# Adafruit_SMT_Datalogger_Shield_rev_C.net
KiCad netlist of a schematic drawn in Altium Designer
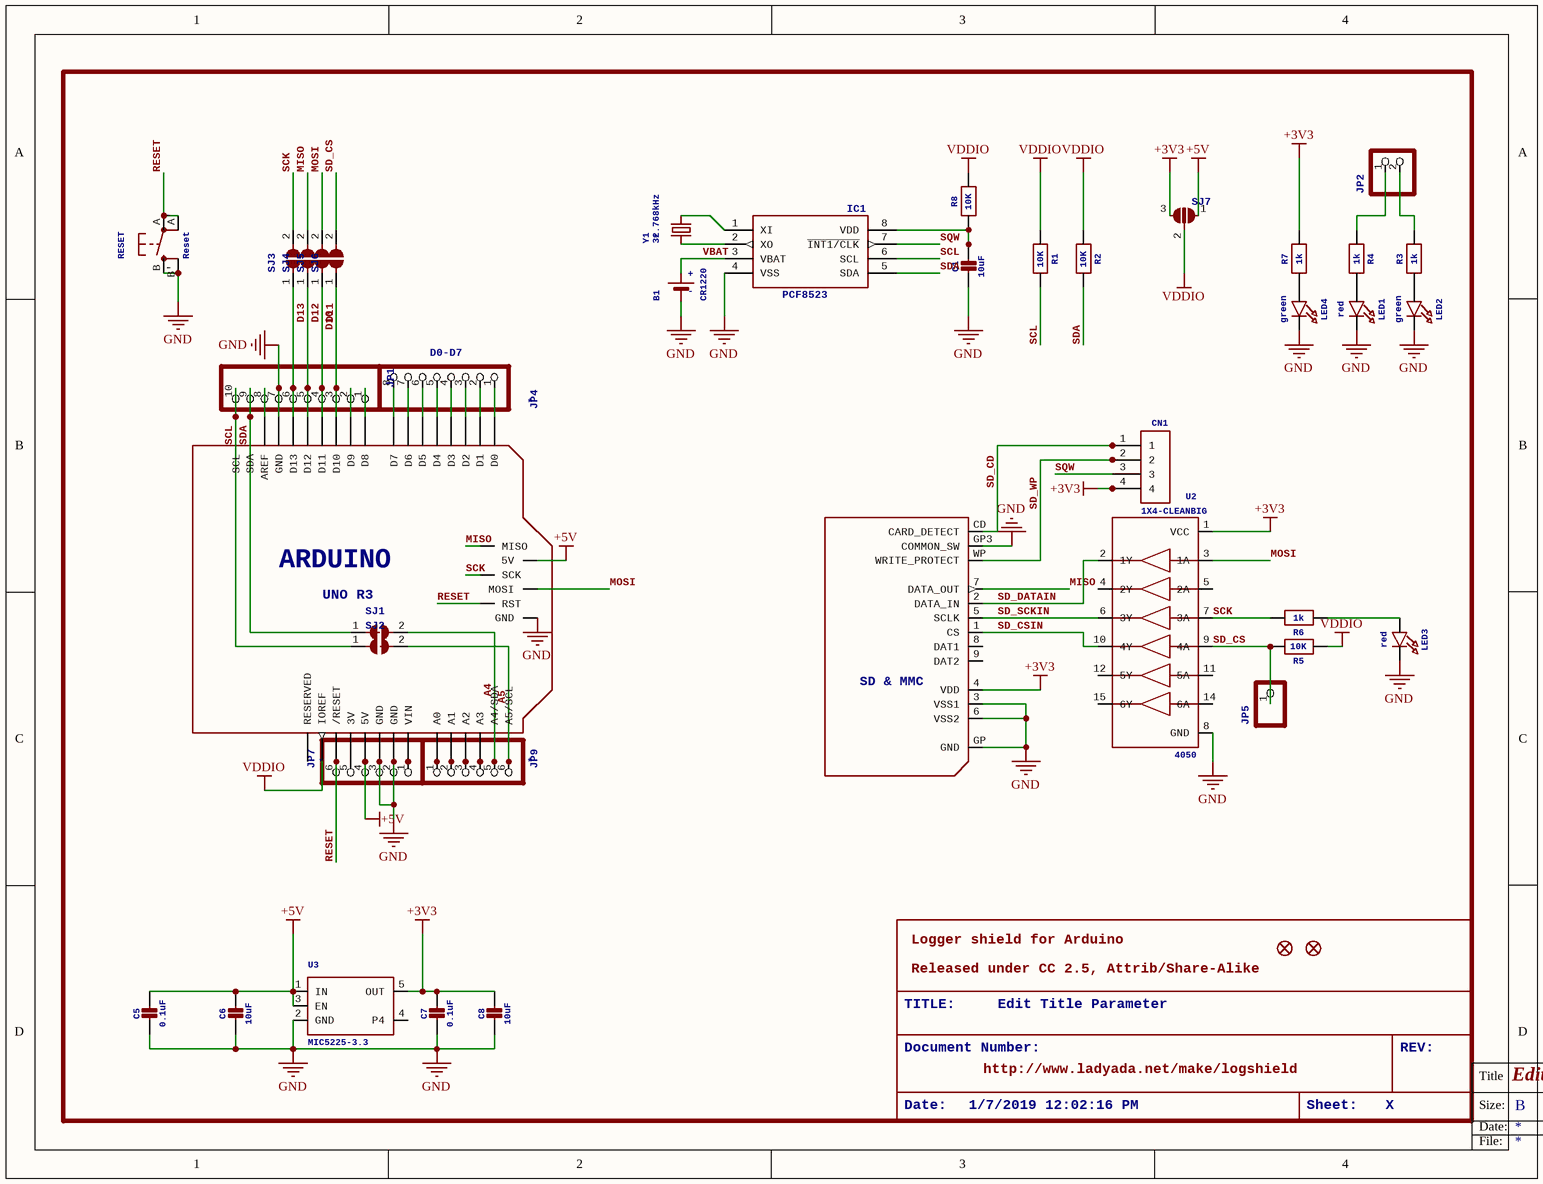
[diagram p0: Adafruit SMT Datalogger Shield rev C.SchDoc]

(export (version "E")
  (design (tool "Eeschema 10.0.6"))
  (components
    (comp (ref "B1")
      (value "CR1220")
      (footprint "CR1220")
      (fields (field (name "+") "+") (field (name "-") "-"))
      (libsource (lib "microbuilder") (part "BATTERYCR1220_SMT"))
    )
    (comp (ref "C1")
      (value "10uF")
      (footprint "0805-NO")
      (libsource (lib "microbuilder") (part "CAP_CERAMIC0805-NOOUTLINE"))
    )
    (comp (ref "C5")
      (value "0.1uF")
      (footprint "0805-NO")
      (libsource (lib "microbuilder") (part "CAP_CERAMIC0805-NOOUTLINE"))
    )
    (comp (ref "C6")
      (value "10uF")
      (footprint "0805-NO")
      (libsource (lib "microbuilder") (part "CAP_CERAMIC0805-NOOUTLINE"))
    )
    (comp (ref "C7")
      (value "0.1uF")
      (footprint "0805-NO")
      (libsource (lib "microbuilder") (part "CAP_CERAMIC0805-NOOUTLINE"))
    )
    (comp (ref "C8")
      (value "10uF")
      (footprint "0805-NO")
      (libsource (lib "microbuilder") (part "CAP_CERAMIC0805-NOOUTLINE"))
    )
    (comp (ref "CN1")
      (value "1X4-CLEANBIG")
      (footprint "1X04-CLEANBIG")
      (description "4-pin connector")
      (libsource (lib "adafruit") (part "1X4-CLEANBIG"))
    )
    (comp (ref "FID1")
      (value "FIDUCIAL_1MM")
      (footprint "FIDUCIAL_1MM")
      (description "Fiducial Alignment PointsVarious fiducial points for machine vision alignment.")
      (libsource (lib "microbuilder") (part "FIDUCIAL_1MM"))
    )
    (comp (ref "FID3")
      (value "FIDUCIAL_1MM")
      (footprint "FIDUCIAL_1MM")
      (description "Fiducial Alignment PointsVarious fiducial points for machine vision alignment.")
      (libsource (lib "microbuilder") (part "FIDUCIAL_1MM"))
    )
    (comp (ref "IC1")
      (value "PCF8523T")
      (footprint "SOIC8_150MIL")
      (fields (field (name "PCF8523") "PCF8523"))
      (libsource (lib "microbuilder") (part "RTC_PCF8523T"))
    )
    (comp (ref "JP1")
      (value "HEADER-1X1070MIL")
      (footprint "1X10_ROUND70")
      (description "PIN HEADER")
      (libsource (lib "microbuilder") (part "HEADER-1X1070MIL"))
    )
    (comp (ref "JP2")
      (value "HEADER-1X2ROUND")
      (footprint "1X02_ROUND")
      (description "PIN HEADER")
      (libsource (lib "microbuilder") (part "HEADER-1X2ROUND"))
    )
    (comp (ref "JP4")
      (value "D0-D7")
      (footprint "1X08-BIG")
      (description "PIN HEADER")
      (fields (field (name "NAME") "*"))
      (libsource (lib "adafruit") (part "PINHD-1X8BIG"))
    )
    (comp (ref "JP5")
      (value "HEADER-1X1ROUND")
      (footprint "1X01_ROUND")
      (description "PIN HEADER")
      (libsource (lib "microbuilder") (part "HEADER-1X1ROUND"))
    )
    (comp (ref "JP7")
      (value "PINHD-1X6B")
      (footprint "1X06-BIG")
      (description "PIN HEADER")
      (fields (field (name "NAME") "*"))
      (libsource (lib "adafruit") (part "PINHD-1X6B"))
    )
    (comp (ref "JP9")
      (value "PINHD-1X6B")
      (footprint "1X06-BIG")
      (description "PIN HEADER")
      (fields (field (name "NAME") "*"))
      (libsource (lib "adafruit") (part "PINHD-1X6B"))
    )
    (comp (ref "LED1")
      (value "red")
      (footprint "CHIPLED_0805_NOOUTLINE")
      (libsource (lib "microbuilder") (part "LED0805_NOOUTLINE"))
    )
    (comp (ref "LED2")
      (value "green")
      (footprint "CHIPLED_0805_NOOUTLINE")
      (libsource (lib "microbuilder") (part "LED0805_NOOUTLINE"))
    )
    (comp (ref "LED3")
      (value "red")
      (footprint "CHIPLED_0805_NOOUTLINE")
      (libsource (lib "microbuilder") (part "LED0805_NOOUTLINE"))
    )
    (comp (ref "LED4")
      (value "green")
      (footprint "CHIPLED_0805_NOOUTLINE")
      (libsource (lib "microbuilder") (part "LED0805_NOOUTLINE"))
    )
    (comp (ref "M1")
      (value "ARDUINO_R3_ICSP_NODIM")
      (footprint "ARDUINOR3_ICSP_NODIM")
      (fields (field (name "ARDUINO") "ARDUINO") (field (name "UNOR3") "UNO R3"))
      (libsource (lib "adafruit") (part "ARDUINO_R3_ICSP_NODIM"))
    )
    (comp (ref "R1")
      (value "10K")
      (footprint "0805-NO")
      (libsource (lib "microbuilder") (part "RESISTOR0805_NOOUTLINE"))
    )
    (comp (ref "R2")
      (value "10K")
      (footprint "0805-NO")
      (libsource (lib "microbuilder") (part "RESISTOR0805_NOOUTLINE"))
    )
    (comp (ref "R3")
      (value "1k")
      (footprint "0805-NO")
      (libsource (lib "microbuilder") (part "RESISTOR0805_NOOUTLINE"))
    )
    (comp (ref "R4")
      (value "1k")
      (footprint "0805-NO")
      (libsource (lib "microbuilder") (part "RESISTOR0805_NOOUTLINE"))
    )
    (comp (ref "R5")
      (value "10K")
      (footprint "0805-NO")
      (libsource (lib "microbuilder") (part "RESISTOR0805_NOOUTLINE"))
    )
    (comp (ref "R6")
      (value "1k")
      (footprint "0805-NO")
      (libsource (lib "microbuilder") (part "RESISTOR0805_NOOUTLINE"))
    )
    (comp (ref "R7")
      (value "1k")
      (footprint "0805-NO")
      (libsource (lib "microbuilder") (part "RESISTOR0805_NOOUTLINE"))
    )
    (comp (ref "R8")
      (value "10K")
      (footprint "0805-NO")
      (libsource (lib "microbuilder") (part "RESISTOR0805_NOOUTLINE"))
    )
    (comp (ref "RESET")
      (value "Reset")
      (footprint "EVQ-Q2_SMALLER")
      (description "SMT Tact Switches")
      (libsource (lib "microbuilder") (part "SWITCH_TACT_SMT_EVQQ2_SMALL"))
    )
    (comp (ref "SJ1")
      (value "SOLDERJUMPER")
      (footprint "SOLDERJUMPER_ARROW_NOPASTE")
      (libsource (lib "microbuilder") (part "SOLDERJUMPER"))
    )
    (comp (ref "SJ2")
      (value "SOLDERJUMPER")
      (footprint "SOLDERJUMPER_ARROW_NOPASTE")
      (libsource (lib "microbuilder") (part "SOLDERJUMPER"))
    )
    (comp (ref "SJ3")
      (value "SOLDERJUMPER")
      (footprint "SOLDERJUMPER_ARROW_NOPASTE")
      (libsource (lib "microbuilder") (part "SOLDERJUMPER"))
    )
    (comp (ref "SJ4")
      (value "SOLDERJUMPER")
      (footprint "SOLDERJUMPER_ARROW_NOPASTE")
      (libsource (lib "microbuilder") (part "SOLDERJUMPER"))
    )
    (comp (ref "SJ5")
      (value "SOLDERJUMPER")
      (footprint "SOLDERJUMPER_ARROW_NOPASTE")
      (libsource (lib "microbuilder") (part "SOLDERJUMPER"))
    )
    (comp (ref "SJ6")
      (value "SOLDERJUMPERCLOSED")
      (footprint "SOLDERJUMPER_CLOSEDWIRE")
      (libsource (lib "microbuilder") (part "SOLDERJUMPERCLOSED"))
    )
    (comp (ref "SJ7")
      (value "SOLDERJUMPER_2WAY")
      (footprint "SOLDERJUMPER_2WAY_OPEN_NOPASTE")
      (description "2-Way Solder Jumper")
      (libsource (lib "microbuilder") (part "SOLDERJUMPER_2WAY"))
    )
    (comp (ref "U$2")
      (value "SDMMC06132")
      (footprint "06132")
      (description "SD MMC Card holder4UCON part #06132 - easy to solder")
      (fields (field (name "SD&MMC") "SD & MMC"))
      (libsource (lib "microbuilder") (part "SDMMC06132"))
    )
    (comp (ref "U2")
      (value "4050")
      (footprint "SOIC16")
      (description "6-channel level shifter 74HC4050D - 2V-6V SupplySOIC16TSSOP16")
      (libsource (lib "microbuilder") (part "74HC4050D"))
    )
    (comp (ref "U3")
      (value "MIC5225-3.3")
      (footprint "SOT23-5")
      (libsource (lib "microbuilder") (part "VREG_SOT23-5"))
    )
    (comp (ref "Y1")
      (value "32.768kHz")
      (footprint "CRYSTAL_8X3.8")
      (fields (field (name "NAME") "*"))
      (libsource (lib "microbuilder") (part "CRYSTAL8.0X3.8"))
    )
  )
  (nets
    (net (code "1") (name "+3V3") (class "Default")
      (node (ref "C7") (pin "1") (pinfunction "1_1") (pintype "passive"))
      (node (ref "C8") (pin "1") (pinfunction "1_1") (pintype "passive"))
      (node (ref "CN1") (pin "4") (pinfunction "4_4") (pintype "passive"))
      (node (ref "R7") (pin "2") (pinfunction "2_2") (pintype "passive"))
      (node (ref "SJ7") (pin "3") (pinfunction "3_3") (pintype "passive"))
      (node (ref "U$2") (pin "4") (pinfunction "VDD_4") (pintype "open_emitter"))
      (node (ref "U2") (pin "1") (pinfunction "VCC_1") (pintype "passive"))
      (node (ref "U3") (pin "5") (pinfunction "OUT_5") (pintype "open_emitter"))
    )
    (net (code "2") (name "+5V") (class "Default")
      (node (ref "C5") (pin "1") (pinfunction "1_1") (pintype "passive"))
      (node (ref "C6") (pin "1") (pinfunction "1_1") (pintype "passive"))
      (node (ref "JP7") (pin "4") (pinfunction "4_4") (pintype "passive"))
      (node (ref "M1") (pin "5V") (pinfunction "5V_5V") (pintype "power_in"))
      (node (ref "M1") (pin "5V_ICSP") (pinfunction "5V_5V_ICSP") (pintype "passive"))
      (node (ref "SJ7") (pin "1") (pinfunction "1_1") (pintype "passive"))
      (node (ref "U3") (pin "1") (pinfunction "IN_1") (pintype "power_in"))
      (node (ref "U3") (pin "3") (pinfunction "EN_3") (pintype "passive"))
    )
    (net (code "3") (name "/A4") (class "Default")
      (node (ref "JP9") (pin "5") (pinfunction "5_5") (pintype "passive"))
      (node (ref "M1") (pin "A4") (pinfunction "A4/SDA_A4") (pintype "passive"))
      (node (ref "SJ1") (pin "2") (pinfunction "2_2") (pintype "passive"))
    )
    (net (code "4") (name "/A5") (class "Default")
      (node (ref "JP9") (pin "6") (pinfunction "6_6") (pintype "passive"))
      (node (ref "M1") (pin "A5") (pinfunction "A5/SCL_A5") (pintype "passive"))
      (node (ref "SJ2") (pin "2") (pinfunction "2_2") (pintype "passive"))
    )
    (net (code "5") (name "/D10") (class "Default")
      (node (ref "JP1") (pin "3") (pinfunction "3_3") (pintype "passive"))
      (node (ref "M1") (pin "D10") (pinfunction "D10_D10") (pintype "passive"))
      (node (ref "SJ6") (pin "1") (pinfunction "1_1") (pintype "passive"))
    )
    (net (code "6") (name "/D11") (class "Default")
      (node (ref "JP1") (pin "4") (pinfunction "4_4") (pintype "passive"))
      (node (ref "M1") (pin "D11") (pinfunction "D11_D11") (pintype "passive"))
      (node (ref "SJ5") (pin "1") (pinfunction "1_1") (pintype "passive"))
    )
    (net (code "7") (name "/D12") (class "Default")
      (node (ref "JP1") (pin "5") (pinfunction "5_5") (pintype "passive"))
      (node (ref "M1") (pin "D12") (pinfunction "D12_D12") (pintype "passive"))
      (node (ref "SJ4") (pin "1") (pinfunction "1_1") (pintype "passive"))
    )
    (net (code "8") (name "/D13") (class "Default")
      (node (ref "JP1") (pin "6") (pinfunction "6_6") (pintype "passive"))
      (node (ref "M1") (pin "D13") (pinfunction "D13_D13") (pintype "passive"))
      (node (ref "SJ3") (pin "1") (pinfunction "1_1") (pintype "passive"))
    )
    (net (code "9") (name "/MISO") (class "Default")
      (node (ref "M1") (pin "MISO") (pinfunction "MISO_MISO") (pintype "passive"))
      (node (ref "SJ4") (pin "2") (pinfunction "2_2") (pintype "passive"))
      (node (ref "U$2") (pin "7") (pinfunction "DATA_OUT_7") (pintype "output"))
    )
    (net (code "10") (name "/MOSI") (class "Default")
      (node (ref "M1") (pin "MOSI") (pinfunction "MOSI_MOSI") (pintype "passive"))
      (node (ref "SJ5") (pin "2") (pinfunction "2_2") (pintype "passive"))
      (node (ref "U2") (pin "3") (pinfunction "1A_3") (pintype "passive"))
    )
    (net (code "11") (name "/RESET") (class "Default")
      (node (ref "JP7") (pin "6") (pinfunction "6_6") (pintype "passive"))
      (node (ref "M1") (pin "RESET") (pinfunction "/RESET_RESET") (pintype "passive"))
      (node (ref "M1") (pin "RESET_ICSP") (pinfunction "RST_RESET_ICSP") (pintype "passive"))
      (node (ref "RESET") (pin "A") (pinfunction "P_A") (pintype "passive"))
      (node (ref "RESET") (pin "A'") (pinfunction "P1_A'") (pintype "passive"))
    )
    (net (code "12") (name "/SCK") (class "Default")
      (node (ref "M1") (pin "SCK") (pinfunction "SCK_SCK") (pintype "passive"))
      (node (ref "R6") (pin "2") (pinfunction "2_2") (pintype "passive"))
      (node (ref "SJ3") (pin "2") (pinfunction "2_2") (pintype "passive"))
      (node (ref "U2") (pin "7") (pinfunction "3A_7") (pintype "passive"))
    )
    (net (code "13") (name "/SCL") (class "Default")
      (node (ref "IC1") (pin "6") (pinfunction "SCL_6") (pintype "passive"))
      (node (ref "JP1") (pin "10") (pinfunction "10_10") (pintype "passive"))
      (node (ref "M1") (pin "SCL") (pinfunction "SCL_SCL") (pintype "passive"))
      (node (ref "R1") (pin "2") (pinfunction "2_2") (pintype "passive"))
      (node (ref "SJ2") (pin "1") (pinfunction "1_1") (pintype "passive"))
    )
    (net (code "14") (name "/SDA") (class "Default")
      (node (ref "IC1") (pin "5") (pinfunction "SDA_5") (pintype "passive"))
      (node (ref "JP1") (pin "9") (pinfunction "9_9") (pintype "passive"))
      (node (ref "M1") (pin "SDA") (pinfunction "SDA_SDA") (pintype "passive"))
      (node (ref "R2") (pin "2") (pinfunction "2_2") (pintype "passive"))
      (node (ref "SJ1") (pin "1") (pinfunction "1_1") (pintype "passive"))
    )
    (net (code "15") (name "/SD_CD") (class "Default")
      (node (ref "CN1") (pin "1") (pinfunction "1_1") (pintype "passive"))
      (node (ref "U$2") (pin "CD") (pinfunction "CARD_DETECT_CD") (pintype "passive"))
    )
    (net (code "16") (name "/SD_CS") (class "Default")
      (node (ref "JP5") (pin "1") (pinfunction "1_1") (pintype "passive"))
      (node (ref "R5") (pin "2") (pinfunction "2_2") (pintype "passive"))
      (node (ref "SJ6") (pin "2") (pinfunction "2_2") (pintype "passive"))
      (node (ref "U2") (pin "9") (pinfunction "4A_9") (pintype "passive"))
    )
    (net (code "17") (name "/SD_CSIN") (class "Default")
      (node (ref "U$2") (pin "1") (pinfunction "CS_1") (pintype "passive"))
      (node (ref "U2") (pin "10") (pinfunction "4Y_10") (pintype "passive"))
    )
    (net (code "18") (name "/SD_DATAIN") (class "Default")
      (node (ref "U$2") (pin "2") (pinfunction "DATA_IN_2") (pintype "passive"))
      (node (ref "U2") (pin "2") (pinfunction "1Y_2") (pintype "passive"))
    )
    (net (code "19") (name "/SD_SCKIN") (class "Default")
      (node (ref "U$2") (pin "5") (pinfunction "SCLK_5") (pintype "passive"))
      (node (ref "U2") (pin "6") (pinfunction "3Y_6") (pintype "passive"))
    )
    (net (code "20") (name "/SD_WP") (class "Default")
      (node (ref "CN1") (pin "2") (pinfunction "2_2") (pintype "passive"))
      (node (ref "U$2") (pin "WP") (pinfunction "WRITE_PROTECT_WP") (pintype "passive"))
    )
    (net (code "21") (name "/SQW") (class "Default")
      (node (ref "CN1") (pin "3") (pinfunction "3_3") (pintype "passive"))
      (node (ref "IC1") (pin "7") (pinfunction "~{INT1/CLK}_7") (pintype "output"))
    )
    (net (code "22") (name "/VBAT") (class "Default")
      (node (ref "B1") (pin "+$1_+$2") (pinfunction "+_+$1_+$2") (pintype "passive"))
      (node (ref "IC1") (pin "3") (pinfunction "VBAT_3") (pintype "power_in"))
    )
    (net (code "23") (name "GND") (class "Default")
      (node (ref "B1") (pin "-") (pinfunction "-_-") (pintype "passive"))
      (node (ref "C1") (pin "2") (pinfunction "2_2") (pintype "passive"))
      (node (ref "C5") (pin "2") (pinfunction "2_2") (pintype "passive"))
      (node (ref "C6") (pin "2") (pinfunction "2_2") (pintype "passive"))
      (node (ref "C7") (pin "2") (pinfunction "2_2") (pintype "passive"))
      (node (ref "C8") (pin "2") (pinfunction "2_2") (pintype "passive"))
      (node (ref "IC1") (pin "4") (pinfunction "VSS_4") (pintype "power_in"))
      (node (ref "JP1") (pin "7") (pinfunction "7_7") (pintype "passive"))
      (node (ref "JP7") (pin "2") (pinfunction "2_2") (pintype "passive"))
      (node (ref "JP7") (pin "3") (pinfunction "3_3") (pintype "passive"))
      (node (ref "LED1") (pin "C") (pinfunction "C_C") (pintype "passive"))
      (node (ref "LED2") (pin "C") (pinfunction "C_C") (pintype "passive"))
      (node (ref "LED3") (pin "C") (pinfunction "C_C") (pintype "passive"))
      (node (ref "LED4") (pin "C") (pinfunction "C_C") (pintype "passive"))
      (node (ref "M1") (pin "GND") (pinfunction "GND_GND") (pintype "power_in"))
      (node (ref "M1") (pin "GND@1") (pinfunction "GND_GND@1") (pintype "power_in"))
      (node (ref "M1") (pin "GND@2") (pinfunction "GND_GND@2") (pintype "passive"))
      (node (ref "M1") (pin "GND@3") (pinfunction "GND_GND@3") (pintype "power_in"))
      (node (ref "RESET") (pin "B") (pinfunction "S_B") (pintype "passive"))
      (node (ref "RESET") (pin "B'") (pinfunction "S1_B'") (pintype "passive"))
      (node (ref "U$2") (pin "3") (pinfunction "VSS1_3") (pintype "open_emitter"))
      (node (ref "U$2") (pin "6") (pinfunction "VSS2_6") (pintype "open_emitter"))
      (node (ref "U$2") (pin "GP") (pinfunction "GND_GP") (pintype "open_emitter"))
      (node (ref "U$2") (pin "GP3") (pinfunction "COMMON_SW_GP3") (pintype "passive"))
      (node (ref "U2") (pin "8") (pinfunction "GND_8") (pintype "passive"))
      (node (ref "U3") (pin "2") (pinfunction "GND_2") (pintype "power_in"))
    )
    (net (code "24") (name "Net-(IC1-VDD)") (class "Default")
      (node (ref "C1") (pin "1") (pinfunction "1_1") (pintype "passive"))
      (node (ref "IC1") (pin "8") (pinfunction "VDD_8") (pintype "power_in"))
      (node (ref "R8") (pin "1") (pinfunction "1_1") (pintype "passive"))
    )
    (net (code "25") (name "Net-(IC1-XI)") (class "Default")
      (node (ref "IC1") (pin "1") (pinfunction "XI_1") (pintype "passive"))
      (node (ref "Y1") (pin "P$4") (pinfunction "2_P$4") (pintype "passive"))
    )
    (net (code "26") (name "Net-(IC1-XO)") (class "Default")
      (node (ref "IC1") (pin "2") (pinfunction "XO_2") (pintype "output"))
      (node (ref "Y1") (pin "P$1") (pinfunction "1_P$1") (pintype "passive"))
    )
    (net (code "27") (name "Net-(JP1-Pad1)") (class "Default")
      (node (ref "JP1") (pin "1") (pinfunction "1_1") (pintype "passive"))
      (node (ref "M1") (pin "D8") (pinfunction "D8_D8") (pintype "passive"))
    )
    (net (code "28") (name "Net-(JP1-Pad2)") (class "Default")
      (node (ref "JP1") (pin "2") (pinfunction "2_2") (pintype "passive"))
      (node (ref "M1") (pin "D9") (pinfunction "D9_D9") (pintype "passive"))
    )
    (net (code "29") (name "Net-(JP1-Pad8)") (class "Default")
      (node (ref "JP1") (pin "8") (pinfunction "8_8") (pintype "passive"))
      (node (ref "M1") (pin "AREF") (pinfunction "AREF_AREF") (pintype "passive"))
    )
    (net (code "30") (name "Net-(JP2-Pad1)") (class "Default")
      (node (ref "JP2") (pin "1") (pinfunction "1_1") (pintype "passive"))
      (node (ref "R4") (pin "1") (pinfunction "1_1") (pintype "passive"))
    )
    (net (code "31") (name "Net-(JP2-Pad2)") (class "Default")
      (node (ref "JP2") (pin "2") (pinfunction "2_2") (pintype "passive"))
      (node (ref "R3") (pin "2") (pinfunction "2_2") (pintype "passive"))
    )
    (net (code "32") (name "Net-(JP4-Pad1)") (class "Default")
      (node (ref "JP4") (pin "1") (pinfunction "1_1") (pintype "passive"))
      (node (ref "M1") (pin "D0") (pinfunction "D0_D0") (pintype "passive"))
    )
    (net (code "33") (name "Net-(JP4-Pad2)") (class "Default")
      (node (ref "JP4") (pin "2") (pinfunction "2_2") (pintype "passive"))
      (node (ref "M1") (pin "D1") (pinfunction "D1_D1") (pintype "passive"))
    )
    (net (code "34") (name "Net-(JP4-Pad3)") (class "Default")
      (node (ref "JP4") (pin "3") (pinfunction "3_3") (pintype "passive"))
      (node (ref "M1") (pin "D2") (pinfunction "D2_D2") (pintype "passive"))
    )
    (net (code "35") (name "Net-(JP4-Pad4)") (class "Default")
      (node (ref "JP4") (pin "4") (pinfunction "4_4") (pintype "passive"))
      (node (ref "M1") (pin "D3") (pinfunction "D3_D3") (pintype "passive"))
    )
    (net (code "36") (name "Net-(JP4-Pad5)") (class "Default")
      (node (ref "JP4") (pin "5") (pinfunction "5_5") (pintype "passive"))
      (node (ref "M1") (pin "D4") (pinfunction "D4_D4") (pintype "passive"))
    )
    (net (code "37") (name "Net-(JP4-Pad6)") (class "Default")
      (node (ref "JP4") (pin "6") (pinfunction "6_6") (pintype "passive"))
      (node (ref "M1") (pin "D5") (pinfunction "D5_D5") (pintype "passive"))
    )
    (net (code "38") (name "Net-(JP4-Pad7)") (class "Default")
      (node (ref "JP4") (pin "7") (pinfunction "7_7") (pintype "passive"))
      (node (ref "M1") (pin "D6") (pinfunction "D6_D6") (pintype "passive"))
    )
    (net (code "39") (name "Net-(JP4-Pad8)") (class "Default")
      (node (ref "JP4") (pin "8") (pinfunction "8_8") (pintype "passive"))
      (node (ref "M1") (pin "D7") (pinfunction "D7_D7") (pintype "passive"))
    )
    (net (code "40") (name "Net-(JP7-Pad1)") (class "Default")
      (node (ref "JP7") (pin "1") (pinfunction "1_1") (pintype "passive"))
      (node (ref "M1") (pin "VIN") (pinfunction "VIN_VIN") (pintype "power_in"))
    )
    (net (code "41") (name "Net-(JP7-Pad5)") (class "Default")
      (node (ref "JP7") (pin "5") (pinfunction "5_5") (pintype "passive"))
      (node (ref "M1") (pin "3V") (pinfunction "3V_3V") (pintype "power_in"))
    )
    (net (code "42") (name "Net-(JP9-Pad1)") (class "Default")
      (node (ref "JP9") (pin "1") (pinfunction "1_1") (pintype "passive"))
      (node (ref "M1") (pin "A0") (pinfunction "A0_A0") (pintype "passive"))
    )
    (net (code "43") (name "Net-(JP9-Pad2)") (class "Default")
      (node (ref "JP9") (pin "2") (pinfunction "2_2") (pintype "passive"))
      (node (ref "M1") (pin "A1") (pinfunction "A1_A1") (pintype "passive"))
    )
    (net (code "44") (name "Net-(JP9-Pad3)") (class "Default")
      (node (ref "JP9") (pin "3") (pinfunction "3_3") (pintype "passive"))
      (node (ref "M1") (pin "A2") (pinfunction "A2_A2") (pintype "passive"))
    )
    (net (code "45") (name "Net-(JP9-Pad4)") (class "Default")
      (node (ref "JP9") (pin "4") (pinfunction "4_4") (pintype "passive"))
      (node (ref "M1") (pin "A3") (pinfunction "A3_A3") (pintype "passive"))
    )
    (net (code "46") (name "Net-(LED1-PadA)") (class "Default")
      (node (ref "LED1") (pin "A") (pinfunction "A_A") (pintype "passive"))
      (node (ref "R4") (pin "2") (pinfunction "2_2") (pintype "passive"))
    )
    (net (code "47") (name "Net-(LED2-PadA)") (class "Default")
      (node (ref "LED2") (pin "A") (pinfunction "A_A") (pintype "passive"))
      (node (ref "R3") (pin "1") (pinfunction "1_1") (pintype "passive"))
    )
    (net (code "48") (name "Net-(LED3-PadA)") (class "Default")
      (node (ref "LED3") (pin "A") (pinfunction "A_A") (pintype "passive"))
      (node (ref "R6") (pin "1") (pinfunction "1_1") (pintype "passive"))
    )
    (net (code "49") (name "Net-(LED4-PadA)") (class "Default")
      (node (ref "LED4") (pin "A") (pinfunction "A_A") (pintype "passive"))
      (node (ref "R7") (pin "1") (pinfunction "1_1") (pintype "passive"))
    )
    (net (code "50") (name "VDDIO") (class "Default")
      (node (ref "M1") (pin "IOREF") (pinfunction "IOREF_IOREF") (pintype "output"))
      (node (ref "R1") (pin "1") (pinfunction "1_1") (pintype "passive"))
      (node (ref "R2") (pin "1") (pinfunction "1_1") (pintype "passive"))
      (node (ref "R5") (pin "1") (pinfunction "1_1") (pintype "passive"))
      (node (ref "R8") (pin "2") (pinfunction "2_2") (pintype "passive"))
      (node (ref "SJ7") (pin "2") (pinfunction "2_2") (pintype "passive"))
    )
    (net (code "51") (name "unconnected-(M1-PadRESERVED)") (class "Default")
      (node (ref "M1") (pin "RESERVED") (pinfunction "RESERVED_RESERVED") (pintype "passive"))
    )
    (net (code "52") (name "unconnected-(U$2-DAT1-Pad8)") (class "Default")
      (node (ref "U$2") (pin "8") (pinfunction "DAT1_8") (pintype "passive"))
    )
    (net (code "53") (name "unconnected-(U$2-DAT2-Pad9)") (class "Default")
      (node (ref "U$2") (pin "9") (pinfunction "DAT2_9") (pintype "passive"))
    )
    (net (code "54") (name "unconnected-(U2-2A-Pad5)") (class "Default")
      (node (ref "U2") (pin "5") (pinfunction "2A_5") (pintype "passive"))
    )
    (net (code "55") (name "unconnected-(U2-2Y-Pad4)") (class "Default")
      (node (ref "U2") (pin "4") (pinfunction "2Y_4") (pintype "passive"))
    )
    (net (code "56") (name "unconnected-(U2-5A-Pad11)") (class "Default")
      (node (ref "U2") (pin "11") (pinfunction "5A_11") (pintype "passive"))
    )
    (net (code "57") (name "unconnected-(U2-5Y-Pad12)") (class "Default")
      (node (ref "U2") (pin "12") (pinfunction "5Y_12") (pintype "passive"))
    )
    (net (code "58") (name "unconnected-(U2-6A-Pad14)") (class "Default")
      (node (ref "U2") (pin "14") (pinfunction "6A_14") (pintype "passive"))
    )
    (net (code "59") (name "unconnected-(U2-6Y-Pad15)") (class "Default")
      (node (ref "U2") (pin "15") (pinfunction "6Y_15") (pintype "passive"))
    )
    (net (code "60") (name "unconnected-(U3-P4-Pad4)") (class "Default")
      (node (ref "U3") (pin "4") (pinfunction "P4_4") (pintype "passive"))
    )
  )
)
